# GoL_1_3.net
KiCad netlist of a schematic drawn in EAGLE
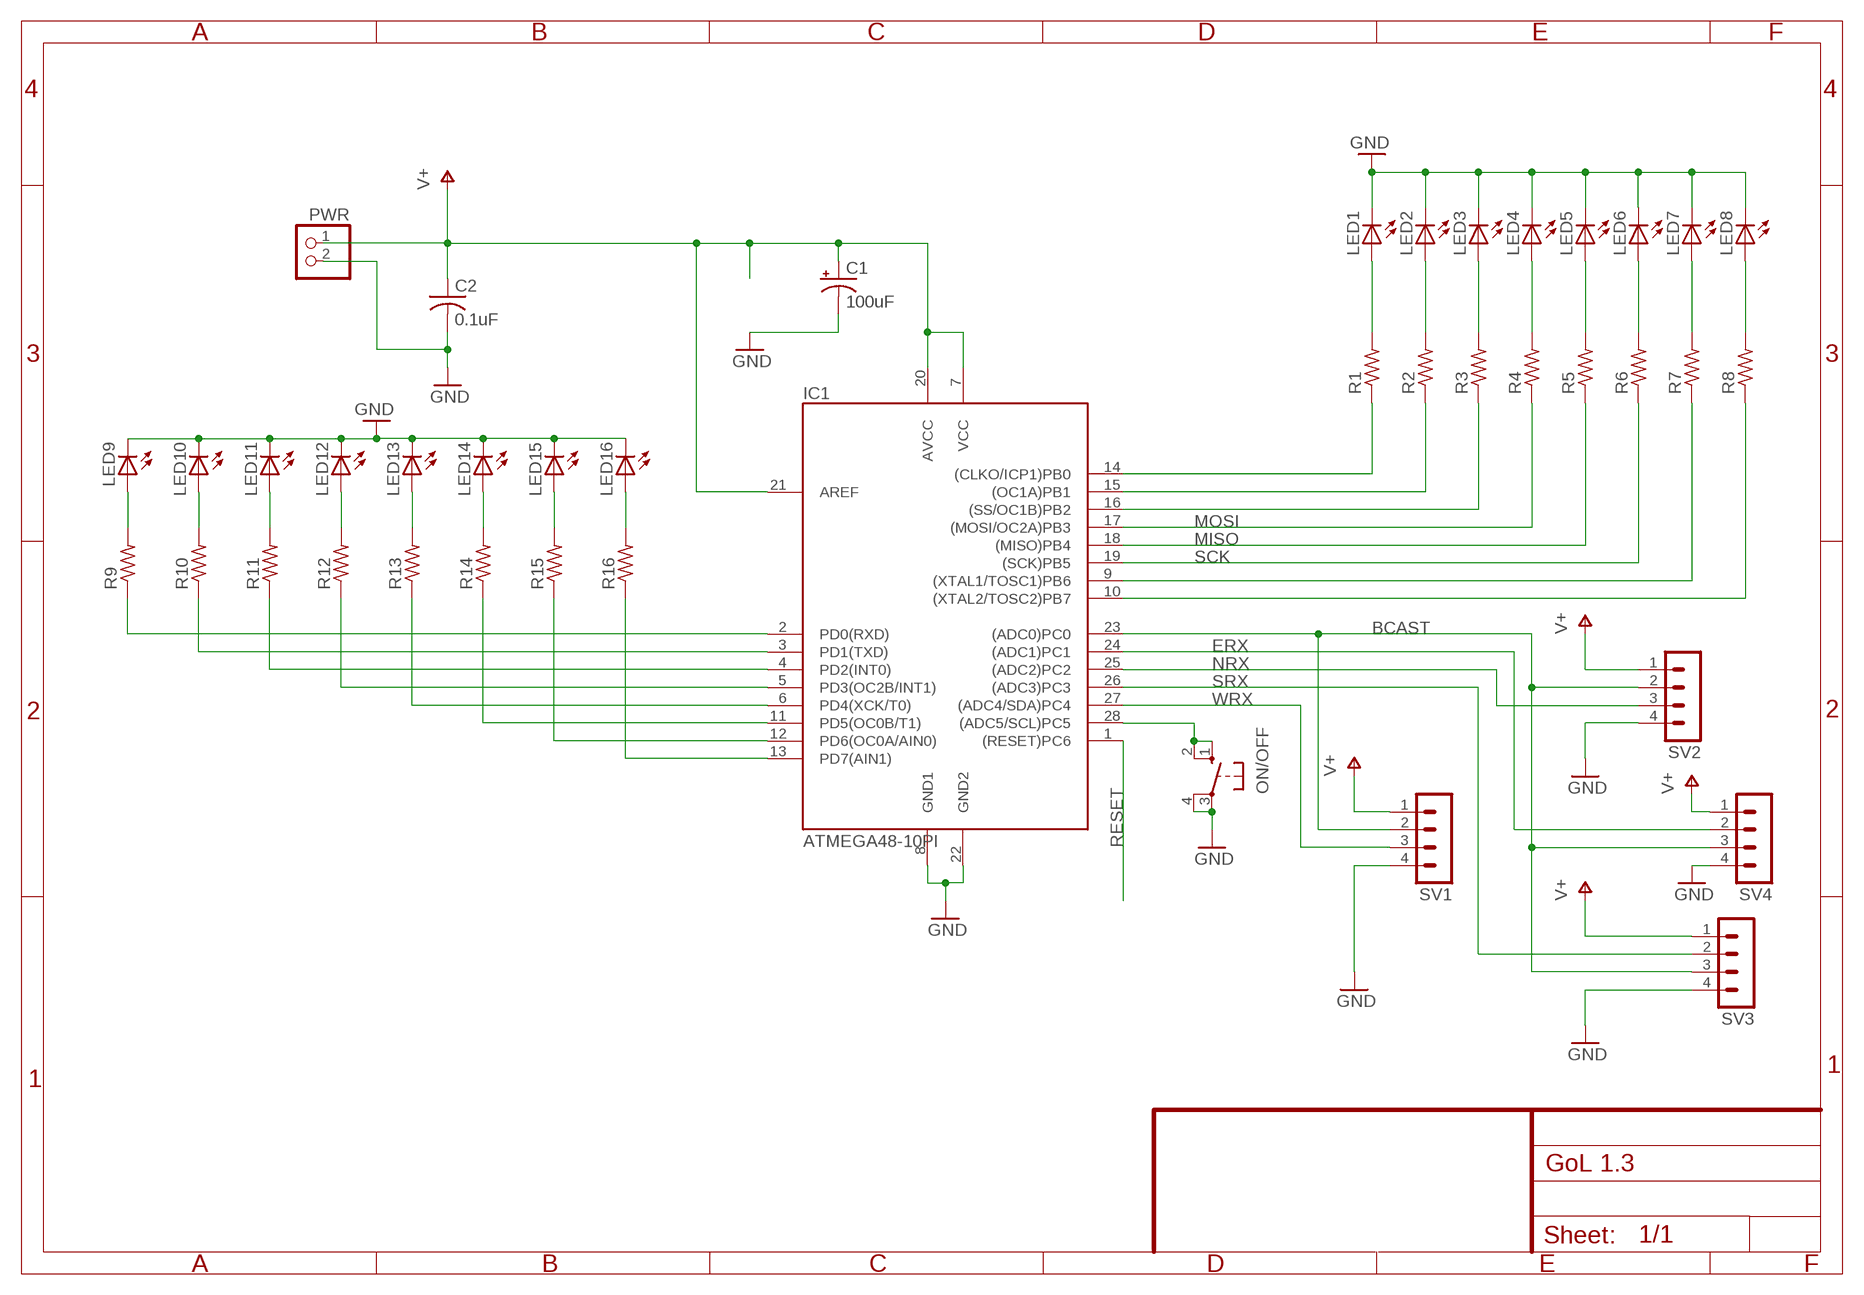
[diagram p0: schematic, sheet 1]

(export (version "E")
  (design (tool "Eeschema 10.0.6"))
  (components
    (comp (ref "C1")
      (value "100uF")
      (footprint "eagle-import:E2,5-6")
      (libsource (lib "eagle-import") (part "CPOL-USE2.5-6"))
    )
    (comp (ref "C2")
      (value "0.1uF")
      (footprint "eagle-import:C025-025X050")
      (libsource (lib "eagle-import") (part "C-US025-025X050"))
    )
    (comp (ref "IC1")
      (value "ATMEGA48-10PI")
      (footprint "eagle-import:DIL28-3")
      (libsource (lib "eagle-import") (part "ATMEGAPI48-10"))
    )
    (comp (ref "LED1")
      (value "LED5MMEZ")
      (footprint "eagle-import:LED5MM-EZ")
      (libsource (lib "eagle-import") (part "LED5MMEZ"))
    )
    (comp (ref "LED2")
      (value "LED5MMEZ")
      (footprint "eagle-import:LED5MM-EZ")
      (libsource (lib "eagle-import") (part "LED5MMEZ"))
    )
    (comp (ref "LED3")
      (value "LED5MMEZ")
      (footprint "eagle-import:LED5MM-EZ")
      (libsource (lib "eagle-import") (part "LED5MMEZ"))
    )
    (comp (ref "LED4")
      (value "LED5MMEZ")
      (footprint "eagle-import:LED5MM-EZ")
      (libsource (lib "eagle-import") (part "LED5MMEZ"))
    )
    (comp (ref "LED5")
      (value "LED5MMEZ")
      (footprint "eagle-import:LED5MM-EZ")
      (libsource (lib "eagle-import") (part "LED5MMEZ"))
    )
    (comp (ref "LED6")
      (value "LED5MMEZ")
      (footprint "eagle-import:LED5MM-EZ")
      (libsource (lib "eagle-import") (part "LED5MMEZ"))
    )
    (comp (ref "LED7")
      (value "LED5MMEZ")
      (footprint "eagle-import:LED5MM-EZ")
      (libsource (lib "eagle-import") (part "LED5MMEZ"))
    )
    (comp (ref "LED8")
      (value "LED5MMEZ")
      (footprint "eagle-import:LED5MM-EZ")
      (libsource (lib "eagle-import") (part "LED5MMEZ"))
    )
    (comp (ref "LED9")
      (value "LED5MMEZ")
      (footprint "eagle-import:LED5MM-EZ")
      (libsource (lib "eagle-import") (part "LED5MMEZ"))
    )
    (comp (ref "LED10")
      (value "LED5MMEZ")
      (footprint "eagle-import:LED5MM-EZ")
      (libsource (lib "eagle-import") (part "LED5MMEZ"))
    )
    (comp (ref "LED11")
      (value "LED5MMEZ")
      (footprint "eagle-import:LED5MM-EZ")
      (libsource (lib "eagle-import") (part "LED5MMEZ"))
    )
    (comp (ref "LED12")
      (value "LED5MMEZ")
      (footprint "eagle-import:LED5MM-EZ")
      (libsource (lib "eagle-import") (part "LED5MMEZ"))
    )
    (comp (ref "LED13")
      (value "LED5MMEZ")
      (footprint "eagle-import:LED5MM-EZ")
      (libsource (lib "eagle-import") (part "LED5MMEZ"))
    )
    (comp (ref "LED14")
      (value "LED5MMEZ")
      (footprint "eagle-import:LED5MM-EZ")
      (libsource (lib "eagle-import") (part "LED5MMEZ"))
    )
    (comp (ref "LED15")
      (value "LED5MMEZ")
      (footprint "eagle-import:LED5MM-EZ")
      (libsource (lib "eagle-import") (part "LED5MMEZ"))
    )
    (comp (ref "LED16")
      (value "LED5MMEZ")
      (footprint "eagle-import:LED5MM-EZ")
      (libsource (lib "eagle-import") (part "LED5MMEZ"))
    )
    (comp (ref "ON/OFF")
      (value "10-XX")
      (footprint "eagle-import:B3F-10XX")
      (libsource (lib "eagle-import") (part "10-XX"))
    )
    (comp (ref "PWR")
      (value "PINHD-1X2")
      (footprint "eagle-import:1X02")
      (libsource (lib "eagle-import") (part "PINHD-1X2"))
    )
    (comp (ref "R1")
      (value "R-US_0207/10")
      (footprint "eagle-import:0207_10")
      (libsource (lib "eagle-import") (part "R-US_0207/10"))
    )
    (comp (ref "R2")
      (value "R-US_0207/10")
      (footprint "eagle-import:0207_10")
      (libsource (lib "eagle-import") (part "R-US_0207/10"))
    )
    (comp (ref "R3")
      (value "R-US_0207/10")
      (footprint "eagle-import:0207_10")
      (libsource (lib "eagle-import") (part "R-US_0207/10"))
    )
    (comp (ref "R4")
      (value "R-US_0207/10")
      (footprint "eagle-import:0207_10")
      (libsource (lib "eagle-import") (part "R-US_0207/10"))
    )
    (comp (ref "R5")
      (value "R-US_0207/10")
      (footprint "eagle-import:0207_10")
      (libsource (lib "eagle-import") (part "R-US_0207/10"))
    )
    (comp (ref "R6")
      (value "R-US_0207/10")
      (footprint "eagle-import:0207_10")
      (libsource (lib "eagle-import") (part "R-US_0207/10"))
    )
    (comp (ref "R7")
      (value "R-US_0207/10")
      (footprint "eagle-import:0207_10")
      (libsource (lib "eagle-import") (part "R-US_0207/10"))
    )
    (comp (ref "R8")
      (value "R-US_0207/10")
      (footprint "eagle-import:0207_10")
      (libsource (lib "eagle-import") (part "R-US_0207/10"))
    )
    (comp (ref "R9")
      (value "R-US_0207/10")
      (footprint "eagle-import:0207_10")
      (libsource (lib "eagle-import") (part "R-US_0207/10"))
    )
    (comp (ref "R10")
      (value "R-US_0207/10")
      (footprint "eagle-import:0207_10")
      (libsource (lib "eagle-import") (part "R-US_0207/10"))
    )
    (comp (ref "R11")
      (value "R-US_0207/10")
      (footprint "eagle-import:0207_10")
      (libsource (lib "eagle-import") (part "R-US_0207/10"))
    )
    (comp (ref "R12")
      (value "R-US_0207/10")
      (footprint "eagle-import:0207_10")
      (libsource (lib "eagle-import") (part "R-US_0207/10"))
    )
    (comp (ref "R13")
      (value "R-US_0207/10")
      (footprint "eagle-import:0207_10")
      (libsource (lib "eagle-import") (part "R-US_0207/10"))
    )
    (comp (ref "R14")
      (value "R-US_0207/10")
      (footprint "eagle-import:0207_10")
      (libsource (lib "eagle-import") (part "R-US_0207/10"))
    )
    (comp (ref "R15")
      (value "R-US_0207/10")
      (footprint "eagle-import:0207_10")
      (libsource (lib "eagle-import") (part "R-US_0207/10"))
    )
    (comp (ref "R16")
      (value "R-US_0207/10")
      (footprint "eagle-import:0207_10")
      (libsource (lib "eagle-import") (part "R-US_0207/10"))
    )
    (comp (ref "SV1")
      (value "MA04-1")
      (footprint "eagle-import:MA04-1")
      (libsource (lib "eagle-import") (part "MA04-1"))
    )
    (comp (ref "SV2")
      (value "MA04-1")
      (footprint "eagle-import:MA04-1")
      (libsource (lib "eagle-import") (part "MA04-1"))
    )
    (comp (ref "SV3")
      (value "MA04-1")
      (footprint "eagle-import:MA04-1")
      (libsource (lib "eagle-import") (part "MA04-1"))
    )
    (comp (ref "SV4")
      (value "MA04-1")
      (footprint "eagle-import:MA04-1")
      (libsource (lib "eagle-import") (part "MA04-1"))
    )
  )
  (nets
    (net (code "1") (name "/BCAST") (class "Default")
      (node (ref "IC1") (pin "23") (pinfunction "(ADC0)PC0_23") (pintype "bidirectional"))
      (node (ref "SV1") (pin "2") (pinfunction "2_2") (pintype "passive"))
      (node (ref "SV2") (pin "2") (pinfunction "2_2") (pintype "passive"))
      (node (ref "SV3") (pin "3") (pinfunction "3_3") (pintype "passive"))
      (node (ref "SV4") (pin "3") (pinfunction "3_3") (pintype "passive"))
    )
    (net (code "2") (name "/ERX") (class "Default")
      (node (ref "IC1") (pin "24") (pinfunction "(ADC1)PC1_24") (pintype "bidirectional"))
      (node (ref "SV4") (pin "2") (pinfunction "2_2") (pintype "passive"))
    )
    (net (code "3") (name "/MISO") (class "Default")
      (node (ref "IC1") (pin "18") (pinfunction "(MISO)PB4_18") (pintype "bidirectional"))
      (node (ref "R5") (pin "1") (pinfunction "1_1") (pintype "passive"))
    )
    (net (code "4") (name "/MOSI") (class "Default")
      (node (ref "IC1") (pin "17") (pinfunction "(MOSI/OC2A)PB3_17") (pintype "bidirectional"))
      (node (ref "R4") (pin "1") (pinfunction "1_1") (pintype "passive"))
    )
    (net (code "5") (name "/NRX") (class "Default")
      (node (ref "IC1") (pin "25") (pinfunction "(ADC2)PC2_25") (pintype "bidirectional"))
      (node (ref "SV2") (pin "3") (pinfunction "3_3") (pintype "passive"))
    )
    (net (code "6") (name "/RESET") (class "Default")
      (node (ref "IC1") (pin "1") (pinfunction "(RESET)PC6_1") (pintype "bidirectional"))
    )
    (net (code "7") (name "/SCK") (class "Default")
      (node (ref "IC1") (pin "19") (pinfunction "(SCK)PB5_19") (pintype "bidirectional"))
      (node (ref "R6") (pin "1") (pinfunction "1_1") (pintype "passive"))
    )
    (net (code "8") (name "/SRX") (class "Default")
      (node (ref "IC1") (pin "26") (pinfunction "(ADC3)PC3_26") (pintype "bidirectional"))
      (node (ref "SV3") (pin "2") (pinfunction "2_2") (pintype "passive"))
    )
    (net (code "9") (name "/WRX") (class "Default")
      (node (ref "IC1") (pin "27") (pinfunction "(ADC4/SDA)PC4_27") (pintype "bidirectional"))
      (node (ref "SV1") (pin "3") (pinfunction "3_3") (pintype "passive"))
    )
    (net (code "10") (name "GND") (class "Default")
      (node (ref "C1") (pin "-") (pinfunction "-_-") (pintype "passive"))
      (node (ref "C2") (pin "2") (pinfunction "2_2") (pintype "passive"))
      (node (ref "IC1") (pin "22") (pinfunction "GND2_22") (pintype "power_in"))
      (node (ref "IC1") (pin "8") (pinfunction "GND1_8") (pintype "power_in"))
      (node (ref "LED1") (pin "K") (pinfunction "C_K") (pintype "passive"))
      (node (ref "LED10") (pin "K") (pinfunction "C_K") (pintype "passive"))
      (node (ref "LED11") (pin "K") (pinfunction "C_K") (pintype "passive"))
      (node (ref "LED12") (pin "K") (pinfunction "C_K") (pintype "passive"))
      (node (ref "LED13") (pin "K") (pinfunction "C_K") (pintype "passive"))
      (node (ref "LED14") (pin "K") (pinfunction "C_K") (pintype "passive"))
      (node (ref "LED15") (pin "K") (pinfunction "C_K") (pintype "passive"))
      (node (ref "LED16") (pin "K") (pinfunction "C_K") (pintype "passive"))
      (node (ref "LED2") (pin "K") (pinfunction "C_K") (pintype "passive"))
      (node (ref "LED3") (pin "K") (pinfunction "C_K") (pintype "passive"))
      (node (ref "LED4") (pin "K") (pinfunction "C_K") (pintype "passive"))
      (node (ref "LED5") (pin "K") (pinfunction "C_K") (pintype "passive"))
      (node (ref "LED6") (pin "K") (pinfunction "C_K") (pintype "passive"))
      (node (ref "LED7") (pin "K") (pinfunction "C_K") (pintype "passive"))
      (node (ref "LED8") (pin "K") (pinfunction "C_K") (pintype "passive"))
      (node (ref "LED9") (pin "K") (pinfunction "C_K") (pintype "passive"))
      (node (ref "ON/OFF") (pin "3") (pinfunction "P_3") (pintype "passive"))
      (node (ref "ON/OFF") (pin "4") (pinfunction "P1_4") (pintype "passive"))
      (node (ref "PWR") (pin "2") (pinfunction "2_2") (pintype "passive"))
      (node (ref "SV1") (pin "4") (pinfunction "4_4") (pintype "passive"))
      (node (ref "SV2") (pin "4") (pinfunction "4_4") (pintype "passive"))
      (node (ref "SV3") (pin "4") (pinfunction "4_4") (pintype "passive"))
      (node (ref "SV4") (pin "4") (pinfunction "4_4") (pintype "passive"))
    )
    (net (code "11") (name "Net-(IC1-(ADC5{slash}SCL)PC5)") (class "Default")
      (node (ref "IC1") (pin "28") (pinfunction "(ADC5/SCL)PC5_28") (pintype "bidirectional"))
      (node (ref "ON/OFF") (pin "1") (pinfunction "S_1") (pintype "passive"))
      (node (ref "ON/OFF") (pin "2") (pinfunction "S1_2") (pintype "passive"))
    )
    (net (code "12") (name "Net-(IC1-(CLKO{slash}ICP1)PB0)") (class "Default")
      (node (ref "IC1") (pin "14") (pinfunction "(CLKO/ICP1)PB0_14") (pintype "bidirectional"))
      (node (ref "R1") (pin "1") (pinfunction "1_1") (pintype "passive"))
    )
    (net (code "13") (name "Net-(IC1-(OC1A)PB1)") (class "Default")
      (node (ref "IC1") (pin "15") (pinfunction "(OC1A)PB1_15") (pintype "bidirectional"))
      (node (ref "R2") (pin "1") (pinfunction "1_1") (pintype "passive"))
    )
    (net (code "14") (name "Net-(IC1-(SS{slash}OC1B)PB2)") (class "Default")
      (node (ref "IC1") (pin "16") (pinfunction "(SS/OC1B)PB2_16") (pintype "bidirectional"))
      (node (ref "R3") (pin "1") (pinfunction "1_1") (pintype "passive"))
    )
    (net (code "15") (name "Net-(IC1-(XTAL1{slash}TOSC1)PB6)") (class "Default")
      (node (ref "IC1") (pin "9") (pinfunction "(XTAL1/TOSC1)PB6_9") (pintype "bidirectional"))
      (node (ref "R7") (pin "1") (pinfunction "1_1") (pintype "passive"))
    )
    (net (code "16") (name "Net-(IC1-(XTAL2{slash}TOSC2)PB7)") (class "Default")
      (node (ref "IC1") (pin "10") (pinfunction "(XTAL2/TOSC2)PB7_10") (pintype "bidirectional"))
      (node (ref "R8") (pin "1") (pinfunction "1_1") (pintype "passive"))
    )
    (net (code "17") (name "Net-(IC1-PD0(RXD))") (class "Default")
      (node (ref "IC1") (pin "2") (pinfunction "PD0(RXD)_2") (pintype "bidirectional"))
      (node (ref "R9") (pin "1") (pinfunction "1_1") (pintype "passive"))
    )
    (net (code "18") (name "Net-(IC1-PD1(TXD))") (class "Default")
      (node (ref "IC1") (pin "3") (pinfunction "PD1(TXD)_3") (pintype "bidirectional"))
      (node (ref "R10") (pin "1") (pinfunction "1_1") (pintype "passive"))
    )
    (net (code "19") (name "Net-(IC1-PD2(INT0))") (class "Default")
      (node (ref "IC1") (pin "4") (pinfunction "PD2(INT0)_4") (pintype "bidirectional"))
      (node (ref "R11") (pin "1") (pinfunction "1_1") (pintype "passive"))
    )
    (net (code "20") (name "Net-(IC1-PD3(OC2B{slash}INT1))") (class "Default")
      (node (ref "IC1") (pin "5") (pinfunction "PD3(OC2B/INT1)_5") (pintype "bidirectional"))
      (node (ref "R12") (pin "1") (pinfunction "1_1") (pintype "passive"))
    )
    (net (code "21") (name "Net-(IC1-PD4(XCK{slash}T0))") (class "Default")
      (node (ref "IC1") (pin "6") (pinfunction "PD4(XCK/T0)_6") (pintype "bidirectional"))
      (node (ref "R13") (pin "1") (pinfunction "1_1") (pintype "passive"))
    )
    (net (code "22") (name "Net-(IC1-PD5(OC0B{slash}T1))") (class "Default")
      (node (ref "IC1") (pin "11") (pinfunction "PD5(OC0B/T1)_11") (pintype "bidirectional"))
      (node (ref "R14") (pin "1") (pinfunction "1_1") (pintype "passive"))
    )
    (net (code "23") (name "Net-(IC1-PD6(OC0A{slash}AIN0))") (class "Default")
      (node (ref "IC1") (pin "12") (pinfunction "PD6(OC0A/AIN0)_12") (pintype "bidirectional"))
      (node (ref "R15") (pin "1") (pinfunction "1_1") (pintype "passive"))
    )
    (net (code "24") (name "Net-(IC1-PD7(AIN1))") (class "Default")
      (node (ref "IC1") (pin "13") (pinfunction "PD7(AIN1)_13") (pintype "bidirectional"))
      (node (ref "R16") (pin "1") (pinfunction "1_1") (pintype "passive"))
    )
    (net (code "25") (name "Net-(LED1-PadA)") (class "Default")
      (node (ref "LED1") (pin "A") (pinfunction "A_A") (pintype "passive"))
      (node (ref "R1") (pin "2") (pinfunction "2_2") (pintype "passive"))
    )
    (net (code "26") (name "Net-(LED2-PadA)") (class "Default")
      (node (ref "LED2") (pin "A") (pinfunction "A_A") (pintype "passive"))
      (node (ref "R2") (pin "2") (pinfunction "2_2") (pintype "passive"))
    )
    (net (code "27") (name "Net-(LED3-PadA)") (class "Default")
      (node (ref "LED3") (pin "A") (pinfunction "A_A") (pintype "passive"))
      (node (ref "R3") (pin "2") (pinfunction "2_2") (pintype "passive"))
    )
    (net (code "28") (name "Net-(LED4-PadA)") (class "Default")
      (node (ref "LED4") (pin "A") (pinfunction "A_A") (pintype "passive"))
      (node (ref "R4") (pin "2") (pinfunction "2_2") (pintype "passive"))
    )
    (net (code "29") (name "Net-(LED5-PadA)") (class "Default")
      (node (ref "LED5") (pin "A") (pinfunction "A_A") (pintype "passive"))
      (node (ref "R5") (pin "2") (pinfunction "2_2") (pintype "passive"))
    )
    (net (code "30") (name "Net-(LED6-PadA)") (class "Default")
      (node (ref "LED6") (pin "A") (pinfunction "A_A") (pintype "passive"))
      (node (ref "R6") (pin "2") (pinfunction "2_2") (pintype "passive"))
    )
    (net (code "31") (name "Net-(LED7-PadA)") (class "Default")
      (node (ref "LED7") (pin "A") (pinfunction "A_A") (pintype "passive"))
      (node (ref "R7") (pin "2") (pinfunction "2_2") (pintype "passive"))
    )
    (net (code "32") (name "Net-(LED8-PadA)") (class "Default")
      (node (ref "LED8") (pin "A") (pinfunction "A_A") (pintype "passive"))
      (node (ref "R8") (pin "2") (pinfunction "2_2") (pintype "passive"))
    )
    (net (code "33") (name "Net-(LED9-PadA)") (class "Default")
      (node (ref "LED9") (pin "A") (pinfunction "A_A") (pintype "passive"))
      (node (ref "R9") (pin "2") (pinfunction "2_2") (pintype "passive"))
    )
    (net (code "34") (name "Net-(LED10-PadA)") (class "Default")
      (node (ref "LED10") (pin "A") (pinfunction "A_A") (pintype "passive"))
      (node (ref "R10") (pin "2") (pinfunction "2_2") (pintype "passive"))
    )
    (net (code "35") (name "Net-(LED11-PadA)") (class "Default")
      (node (ref "LED11") (pin "A") (pinfunction "A_A") (pintype "passive"))
      (node (ref "R11") (pin "2") (pinfunction "2_2") (pintype "passive"))
    )
    (net (code "36") (name "Net-(LED12-PadA)") (class "Default")
      (node (ref "LED12") (pin "A") (pinfunction "A_A") (pintype "passive"))
      (node (ref "R12") (pin "2") (pinfunction "2_2") (pintype "passive"))
    )
    (net (code "37") (name "Net-(LED13-PadA)") (class "Default")
      (node (ref "LED13") (pin "A") (pinfunction "A_A") (pintype "passive"))
      (node (ref "R13") (pin "2") (pinfunction "2_2") (pintype "passive"))
    )
    (net (code "38") (name "Net-(LED14-PadA)") (class "Default")
      (node (ref "LED14") (pin "A") (pinfunction "A_A") (pintype "passive"))
      (node (ref "R14") (pin "2") (pinfunction "2_2") (pintype "passive"))
    )
    (net (code "39") (name "Net-(LED15-PadA)") (class "Default")
      (node (ref "LED15") (pin "A") (pinfunction "A_A") (pintype "passive"))
      (node (ref "R15") (pin "2") (pinfunction "2_2") (pintype "passive"))
    )
    (net (code "40") (name "Net-(LED16-PadA)") (class "Default")
      (node (ref "LED16") (pin "A") (pinfunction "A_A") (pintype "passive"))
      (node (ref "R16") (pin "2") (pinfunction "2_2") (pintype "passive"))
    )
    (net (code "41") (name "V+") (class "Default")
      (node (ref "C1") (pin "+") (pinfunction "+_+") (pintype "passive"))
      (node (ref "C2") (pin "1") (pinfunction "1_1") (pintype "passive"))
      (node (ref "IC1") (pin "20") (pinfunction "AVCC_20") (pintype "power_in"))
      (node (ref "IC1") (pin "21") (pinfunction "AREF_21") (pintype "input"))
      (node (ref "IC1") (pin "7") (pinfunction "VCC_7") (pintype "power_in"))
      (node (ref "PWR") (pin "1") (pinfunction "1_1") (pintype "passive"))
      (node (ref "SV1") (pin "1") (pinfunction "1_1") (pintype "passive"))
      (node (ref "SV2") (pin "1") (pinfunction "1_1") (pintype "passive"))
      (node (ref "SV3") (pin "1") (pinfunction "1_1") (pintype "passive"))
      (node (ref "SV4") (pin "1") (pinfunction "1_1") (pintype "passive"))
    )
  )
)
